# esp8266_wio7c_breakout.net
KiCad netlist of a schematic drawn in EAGLE
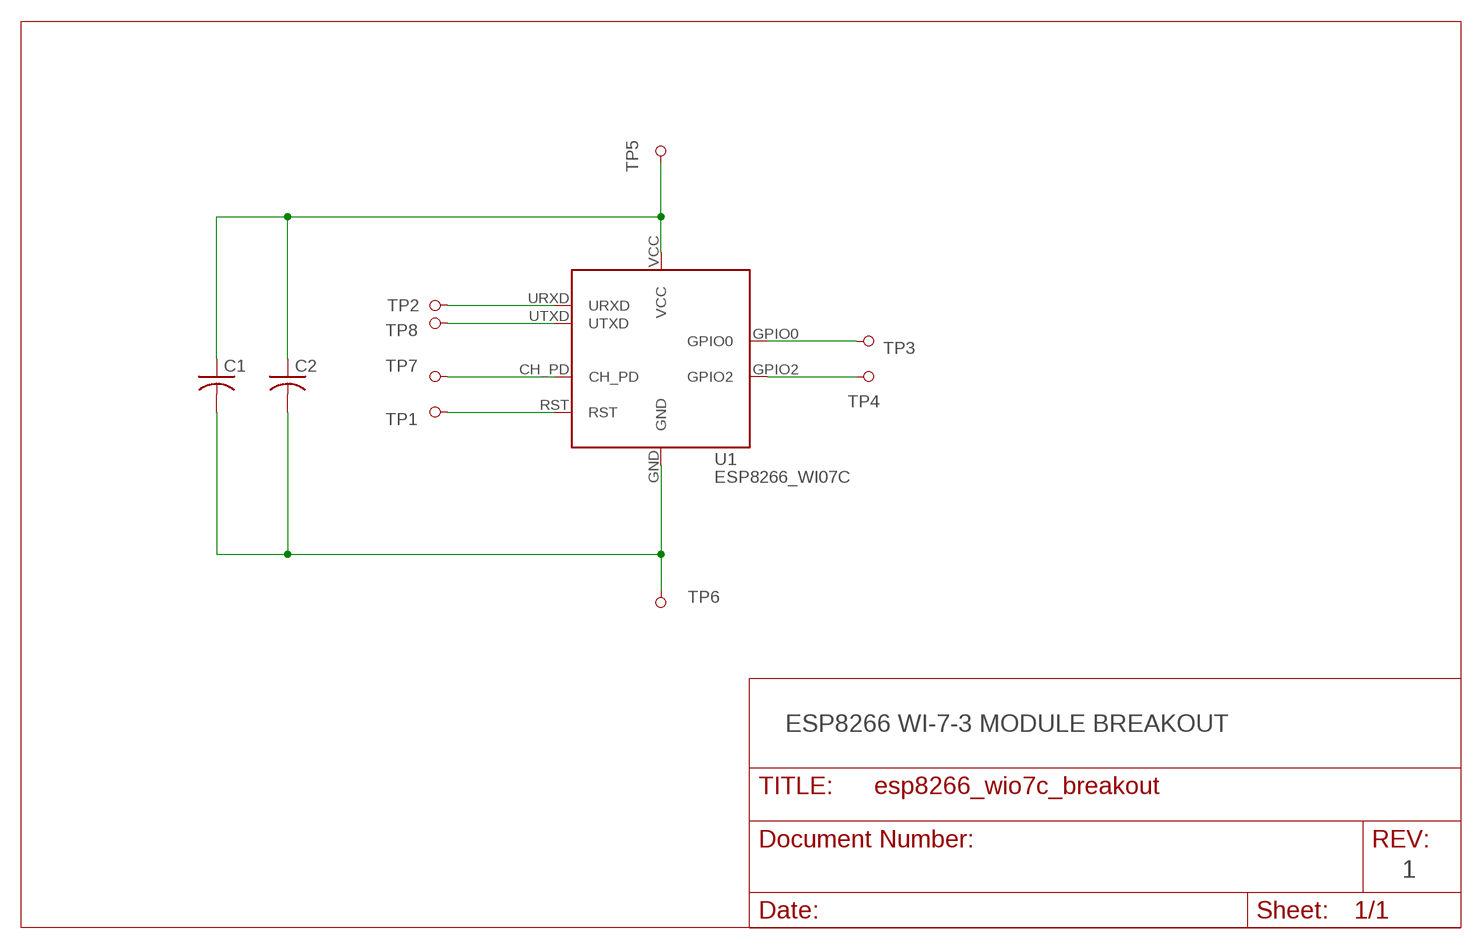
[diagram p0: schematic, sheet 1]

(export (version "E")
  (design (tool "Eeschema 10.0.6"))
  (components
    (comp (ref "C1")
      (value "CAPACITORC0603K")
      (footprint "eagle-import:C0603K")
      (libsource (lib "eagle-import") (part "CAPACITORC0603K"))
    )
    (comp (ref "C2")
      (value "CAPACITORC0603K")
      (footprint "eagle-import:C0603K")
      (libsource (lib "eagle-import") (part "CAPACITORC0603K"))
    )
    (comp (ref "TP1")
      (value "PINHD-1X1")
      (footprint "eagle-import:1X01")
      (libsource (lib "eagle-import") (part "PINHD-1X1"))
    )
    (comp (ref "TP2")
      (value "PINHD-1X1")
      (footprint "eagle-import:1X01")
      (libsource (lib "eagle-import") (part "PINHD-1X1"))
    )
    (comp (ref "TP3")
      (value "PINHD-1X1")
      (footprint "eagle-import:1X01")
      (libsource (lib "eagle-import") (part "PINHD-1X1"))
    )
    (comp (ref "TP4")
      (value "PINHD-1X1")
      (footprint "eagle-import:1X01")
      (libsource (lib "eagle-import") (part "PINHD-1X1"))
    )
    (comp (ref "TP5")
      (value "PINHD-1X1")
      (footprint "eagle-import:1X01")
      (libsource (lib "eagle-import") (part "PINHD-1X1"))
    )
    (comp (ref "TP6")
      (value "PINHD-1X1-FIRST")
      (footprint "eagle-import:1X01_FIRST")
      (libsource (lib "eagle-import") (part "PINHD-1X1-FIRST"))
    )
    (comp (ref "TP7")
      (value "PINHD-1X1")
      (footprint "eagle-import:1X01")
      (libsource (lib "eagle-import") (part "PINHD-1X1"))
    )
    (comp (ref "TP8")
      (value "PINHD-1X1")
      (footprint "eagle-import:1X01")
      (libsource (lib "eagle-import") (part "PINHD-1X1"))
    )
    (comp (ref "U1")
      (value "ESP8266_WI07C")
      (footprint "eagle-import:ESP8266_WI07C")
      (libsource (lib "eagle-import") (part "ESP8266_WI07C"))
    )
  )
  (nets
    (net (code "1") (name "Net-(C1-Pad1)") (class "Default")
      (node (ref "C1") (pin "1") (pinfunction "1_1") (pintype "passive"))
      (node (ref "C2") (pin "1") (pinfunction "1_1") (pintype "passive"))
      (node (ref "TP5") (pin "1") (pinfunction "1_1") (pintype "passive"))
      (node (ref "U1") (pin "VCC") (pinfunction "VCC_VCC") (pintype "power_in"))
    )
    (net (code "2") (name "Net-(C1-Pad2)") (class "Default")
      (node (ref "C1") (pin "2") (pinfunction "2_2") (pintype "passive"))
      (node (ref "C2") (pin "2") (pinfunction "2_2") (pintype "passive"))
      (node (ref "TP6") (pin "1") (pinfunction "1_1") (pintype "passive"))
      (node (ref "U1") (pin "GND") (pinfunction "GND_GND") (pintype "power_in"))
    )
    (net (code "3") (name "Net-(TP1-Pad1)") (class "Default")
      (node (ref "TP1") (pin "1") (pinfunction "1_1") (pintype "passive"))
      (node (ref "U1") (pin "RST") (pinfunction "RST_RST") (pintype "input"))
    )
    (net (code "4") (name "Net-(TP2-Pad1)") (class "Default")
      (node (ref "TP2") (pin "1") (pinfunction "1_1") (pintype "passive"))
      (node (ref "U1") (pin "URXD") (pinfunction "URXD_URXD") (pintype "input"))
    )
    (net (code "5") (name "Net-(TP3-Pad1)") (class "Default")
      (node (ref "TP3") (pin "1") (pinfunction "1_1") (pintype "passive"))
      (node (ref "U1") (pin "GPIO0") (pinfunction "GPIO0_GPIO0") (pintype "bidirectional"))
    )
    (net (code "6") (name "Net-(TP4-Pad1)") (class "Default")
      (node (ref "TP4") (pin "1") (pinfunction "1_1") (pintype "passive"))
      (node (ref "U1") (pin "GPIO2") (pinfunction "GPIO2_GPIO2") (pintype "bidirectional"))
    )
    (net (code "7") (name "Net-(TP7-Pad1)") (class "Default")
      (node (ref "TP7") (pin "1") (pinfunction "1_1") (pintype "passive"))
      (node (ref "U1") (pin "CH_PD") (pinfunction "CH_PD_CH_PD") (pintype "input"))
    )
    (net (code "8") (name "Net-(TP8-Pad1)") (class "Default")
      (node (ref "TP8") (pin "1") (pinfunction "1_1") (pintype "passive"))
      (node (ref "U1") (pin "UTXD") (pinfunction "UTXD_UTXD") (pintype "output"))
    )
  )
)
